# fonte.net
KiCad netlist of a schematic drawn in EAGLE
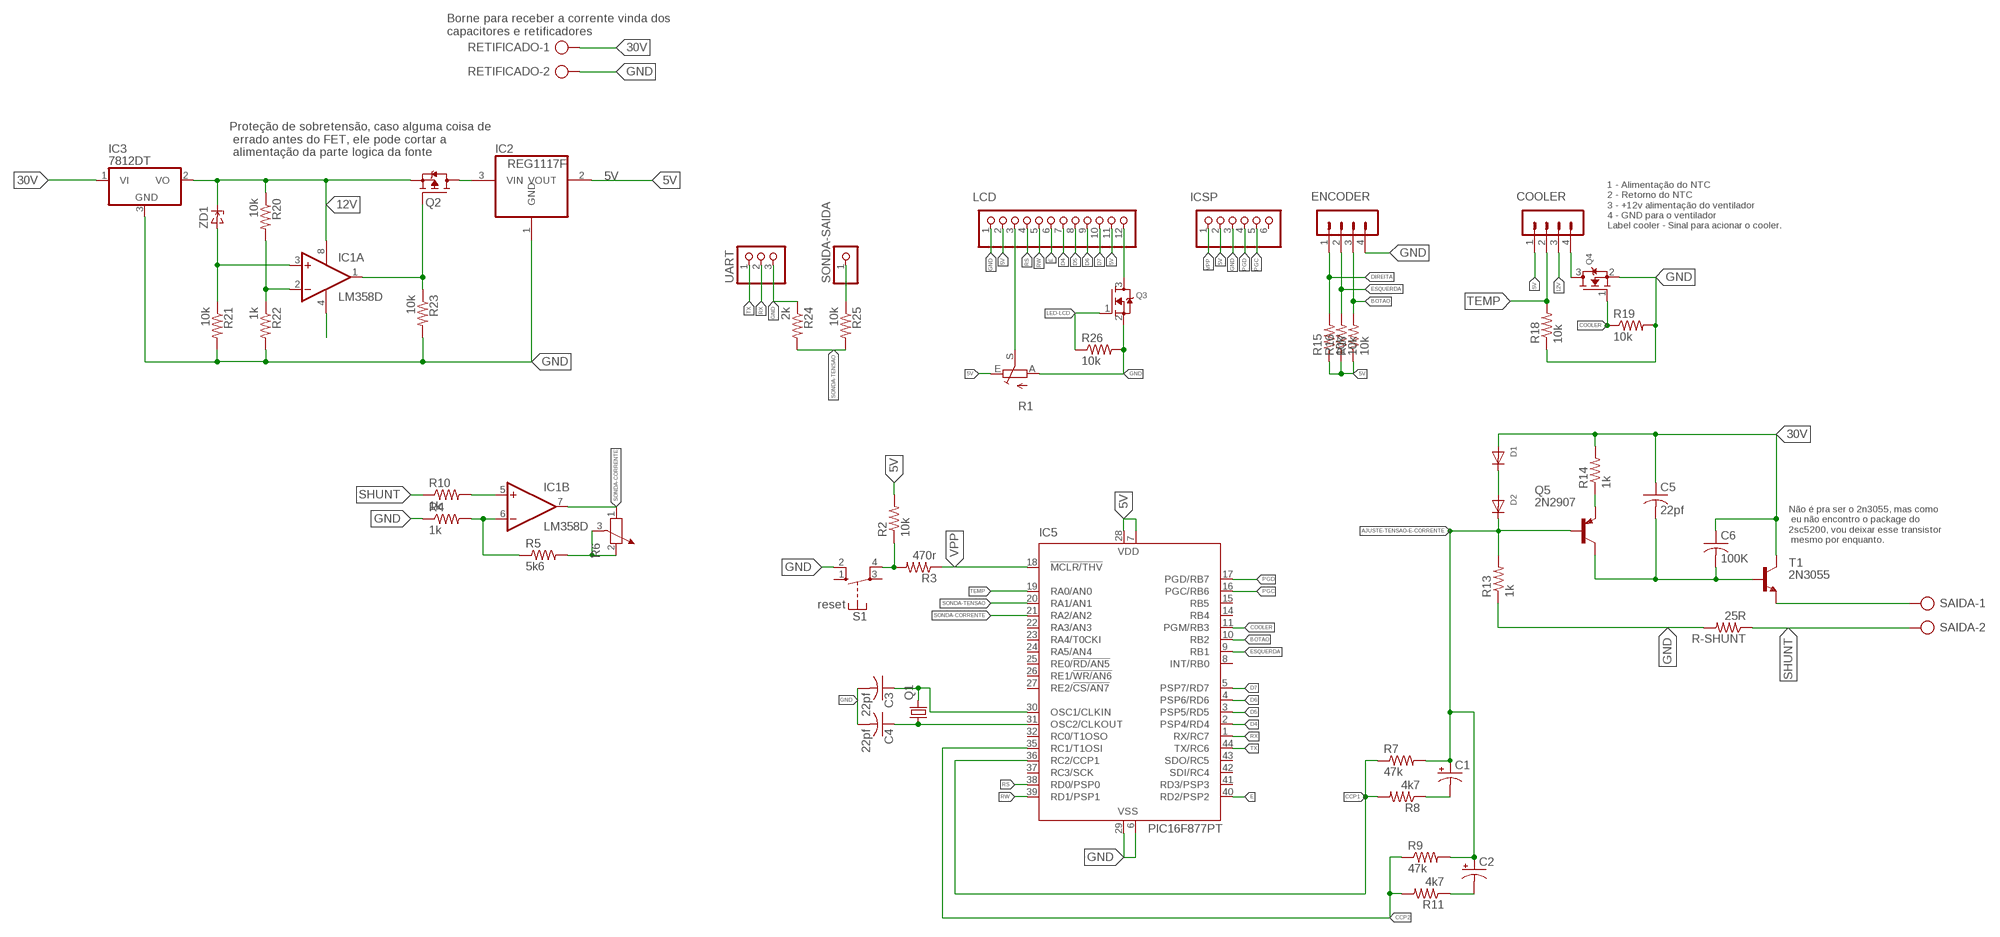
[diagram p0: schematic, sheet 1]

(export (version "E")
  (design (tool "Eeschema 10.0.6"))
  (components
    (comp (ref "C1")
      (value "CPOL-US140CLH-1010")
      (footprint "eagle-import:140CLH-1010")
      (libsource (lib "eagle-import") (part "CPOL-US140CLH-1010"))
    )
    (comp (ref "C2")
      (value "CPOL-US140CLH-1010")
      (footprint "eagle-import:140CLH-1010")
      (libsource (lib "eagle-import") (part "CPOL-US140CLH-1010"))
    )
    (comp (ref "C3")
      (value "22pf")
      (footprint "eagle-import:C1812")
      (libsource (lib "eagle-import") (part "C-USC1812"))
    )
    (comp (ref "C4")
      (value "22pf")
      (footprint "eagle-import:C1812")
      (libsource (lib "eagle-import") (part "C-USC1812"))
    )
    (comp (ref "C5")
      (value "22pf")
      (footprint "eagle-import:C1812")
      (libsource (lib "eagle-import") (part "C-USC1812"))
    )
    (comp (ref "C6")
      (value "100K")
      (footprint "eagle-import:C1812")
      (libsource (lib "eagle-import") (part "C-USC1812"))
    )
    (comp (ref "COOLER")
      (value "MA04-1")
      (footprint "eagle-import:MA04-1")
      (libsource (lib "eagle-import") (part "MA04-1"))
    )
    (comp (ref "D1")
      (value "DIODESOD-123")
      (footprint "eagle-import:SOD-123")
      (libsource (lib "eagle-import") (part "DIODESOD-123"))
    )
    (comp (ref "D2")
      (value "DIODESOD-123")
      (footprint "eagle-import:SOD-123")
      (libsource (lib "eagle-import") (part "DIODESOD-123"))
    )
    (comp (ref "ENCODER")
      (value "MA04-1")
      (footprint "eagle-import:MA04-1")
      (libsource (lib "eagle-import") (part "MA04-1"))
    )
    (comp (ref "IC1")
      (value "LM358D")
      (footprint "eagle-import:SO08")
      (libsource (lib "eagle-import") (part "LM358D"))
    )
    (comp (ref "IC2")
      (value "REG1117F")
      (footprint "eagle-import:DD-3")
      (fields (field (name "MF") "TEXAS INSTRUMENTS") (field (name "MPN") "REG1117FAKTTT"))
      (libsource (lib "eagle-import") (part "REG1117F"))
    )
    (comp (ref "IC3")
      (value "7812DT")
      (footprint "eagle-import:TO252")
      (libsource (lib "eagle-import") (part "78DT12"))
    )
    (comp (ref "IC5")
      (value "PIC16F877PT")
      (footprint "eagle-import:TQFP44")
      (fields (field (name "MF") "MICROCHIP") (field (name "MPN") "PIC16F877-04/PQ"))
      (libsource (lib "eagle-import") (part "PIC16F87PT7"))
    )
    (comp (ref "ICSP")
      (value "PINHD-1X6B")
      (footprint "eagle-import:1X06-BIG")
      (libsource (lib "eagle-import") (part "PINHD-1X6B"))
    )
    (comp (ref "LCD")
      (value "PINHD-1X12-CB")
      (footprint "eagle-import:1X12-CB")
      (libsource (lib "eagle-import") (part "PINHD-1X12-CB"))
    )
    (comp (ref "Q1")
      (value "CRYSTALHC49UP")
      (footprint "eagle-import:HC49UP")
      (libsource (lib "eagle-import") (part "CRYSTALHC49UP"))
    )
    (comp (ref "Q2")
      (value "BSA223SP")
      (footprint "eagle-import:SC75_INFINEON")
      (libsource (lib "eagle-import") (part "BSA223SP"))
    )
    (comp (ref "Q3")
      (value "MOSFET-NREFLOW")
      (footprint "eagle-import:SOT23")
      (libsource (lib "eagle-import") (part "MOSFET-NREFLOW"))
    )
    (comp (ref "Q4")
      (value "MOSFET-NREFLOW")
      (footprint "eagle-import:SOT23")
      (libsource (lib "eagle-import") (part "MOSFET-NREFLOW"))
    )
    (comp (ref "Q5")
      (value "2N2907")
      (footprint "eagle-import:TO92-EBC-OVAL")
      (libsource (lib "eagle-import") (part "2N2907"))
    )
    (comp (ref "R-SHUNT")
      (value "25R")
      (footprint "eagle-import:R0603")
      (libsource (lib "eagle-import") (part "R-US_R0603"))
    )
    (comp (ref "R1")
      (value "TRIM_EU-LI15")
      (footprint "eagle-import:LI15")
      (libsource (lib "eagle-import") (part "TRIM_EU-LI15"))
    )
    (comp (ref "R2")
      (value "10k")
      (footprint "eagle-import:R0603")
      (libsource (lib "eagle-import") (part "R-US_R0603"))
    )
    (comp (ref "R3")
      (value "470r")
      (footprint "eagle-import:R0603")
      (libsource (lib "eagle-import") (part "R-US_R0603"))
    )
    (comp (ref "R4")
      (value "1k")
      (footprint "eagle-import:R0603")
      (libsource (lib "eagle-import") (part "R-US_R0603"))
    )
    (comp (ref "R5")
      (value "5k6")
      (footprint "eagle-import:R0603")
      (libsource (lib "eagle-import") (part "R-US_R0603"))
    )
    (comp (ref "R6")
      (value "POTENTIOMETER_PT-10")
      (footprint "eagle-import:PT-10")
      (libsource (lib "eagle-import") (part "POTENTIOMETER_PT-10"))
    )
    (comp (ref "R7")
      (value "47k")
      (footprint "eagle-import:R0603")
      (libsource (lib "eagle-import") (part "R-US_R0603"))
    )
    (comp (ref "R8")
      (value "4k7")
      (footprint "eagle-import:R0603")
      (libsource (lib "eagle-import") (part "R-US_R0603"))
    )
    (comp (ref "R9")
      (value "47k")
      (footprint "eagle-import:R0603")
      (libsource (lib "eagle-import") (part "R-US_R0603"))
    )
    (comp (ref "R10")
      (value "1k")
      (footprint "eagle-import:R0603")
      (libsource (lib "eagle-import") (part "R-US_R0603"))
    )
    (comp (ref "R11")
      (value "4k7")
      (footprint "eagle-import:R0603")
      (libsource (lib "eagle-import") (part "R-US_R0603"))
    )
    (comp (ref "R13")
      (value "1k")
      (footprint "eagle-import:R0603")
      (libsource (lib "eagle-import") (part "R-US_R0603"))
    )
    (comp (ref "R14")
      (value "1k")
      (footprint "eagle-import:R0603")
      (libsource (lib "eagle-import") (part "R-US_R0603"))
    )
    (comp (ref "R15")
      (value "10k")
      (footprint "eagle-import:R0603")
      (libsource (lib "eagle-import") (part "R-US_R0603"))
    )
    (comp (ref "R16")
      (value "10k")
      (footprint "eagle-import:R0603")
      (libsource (lib "eagle-import") (part "R-US_R0603"))
    )
    (comp (ref "R17")
      (value "10k")
      (footprint "eagle-import:R0603")
      (libsource (lib "eagle-import") (part "R-US_R0603"))
    )
    (comp (ref "R18")
      (value "10k")
      (footprint "eagle-import:R0603")
      (libsource (lib "eagle-import") (part "R-US_R0603"))
    )
    (comp (ref "R19")
      (value "10k")
      (footprint "eagle-import:R0603")
      (libsource (lib "eagle-import") (part "R-US_R0603"))
    )
    (comp (ref "R20")
      (value "10k")
      (footprint "eagle-import:R0603")
      (libsource (lib "eagle-import") (part "R-US_R0603"))
    )
    (comp (ref "R21")
      (value "10k")
      (footprint "eagle-import:R0603")
      (libsource (lib "eagle-import") (part "R-US_R0603"))
    )
    (comp (ref "R22")
      (value "1k")
      (footprint "eagle-import:R0603")
      (libsource (lib "eagle-import") (part "R-US_R0603"))
    )
    (comp (ref "R23")
      (value "10k")
      (footprint "eagle-import:R0603")
      (libsource (lib "eagle-import") (part "R-US_R0603"))
    )
    (comp (ref "R24")
      (value "2k")
      (footprint "eagle-import:R0603")
      (libsource (lib "eagle-import") (part "R-US_R0603"))
    )
    (comp (ref "R25")
      (value "10k")
      (footprint "eagle-import:R0603")
      (libsource (lib "eagle-import") (part "R-US_R0603"))
    )
    (comp (ref "R26")
      (value "10k")
      (footprint "eagle-import:R0603")
      (libsource (lib "eagle-import") (part "R-US_R0603"))
    )
    (comp (ref "RETIFICADO")
      (value "AK300/2")
      (footprint "eagle-import:AK300_2")
      (libsource (lib "eagle-import") (part "AK300/2"))
    )
    (comp (ref "S1")
      (value "reset")
      (footprint "eagle-import:RACON12")
      (libsource (lib "eagle-import") (part "RACON12"))
    )
    (comp (ref "SAIDA")
      (value "AK300/2")
      (footprint "eagle-import:AK300_2")
      (libsource (lib "eagle-import") (part "AK300/2"))
    )
    (comp (ref "SONDA-SAIDA")
      (value "PINHD-1X1")
      (footprint "eagle-import:1X01")
      (libsource (lib "eagle-import") (part "PINHD-1X1"))
    )
    (comp (ref "T1")
      (value "2N3055")
      (footprint "eagle-import:TO3")
      (libsource (lib "eagle-import") (part "2N3055"))
    )
    (comp (ref "UART")
      (value "PINHD-1X3CB")
      (footprint "eagle-import:1X03-CLEANBIG")
      (libsource (lib "eagle-import") (part "PINHD-1X3CB"))
    )
    (comp (ref "ZD1")
      (value "ZENERSOD-123")
      (footprint "eagle-import:SOD-123")
      (libsource (lib "eagle-import") (part "ZENERSOD-123"))
    )
  )
  (nets
    (net (code "1") (name "5V") (class "Default")
      (node (ref "COOLER") (pin "1") (pinfunction "1_1") (pintype "passive"))
      (node (ref "IC2") (pin "2") (pinfunction "VOUT_2") (pintype "output"))
      (node (ref "IC5") (pin "28") (pinfunction "VDD_28") (pintype "power_in"))
      (node (ref "IC5") (pin "7") (pinfunction "VDD_7") (pintype "power_in"))
      (node (ref "ICSP") (pin "2") (pinfunction "2_2") (pintype "passive"))
      (node (ref "LCD") (pin "11") (pinfunction "11_11") (pintype "passive"))
      (node (ref "LCD") (pin "2") (pinfunction "2_2") (pintype "passive"))
      (node (ref "R1") (pin "E") (pinfunction "E_E") (pintype "passive"))
      (node (ref "R15") (pin "1") (pinfunction "1_1") (pintype "passive"))
      (node (ref "R16") (pin "1") (pinfunction "1_1") (pintype "passive"))
      (node (ref "R17") (pin "1") (pinfunction "1_1") (pintype "passive"))
      (node (ref "R2") (pin "2") (pinfunction "2_2") (pintype "passive"))
    )
    (net (code "2") (name "12V") (class "Default")
      (node (ref "COOLER") (pin "3") (pinfunction "3_3") (pintype "passive"))
      (node (ref "IC1") (pin "8") (pinfunction "V+_8") (pintype "power_in"))
      (node (ref "IC3") (pin "2") (pinfunction "VO_2") (pintype "passive"))
      (node (ref "Q2") (pin "3") (pinfunction "S_3") (pintype "passive"))
      (node (ref "R20") (pin "1") (pinfunction "1_1") (pintype "passive"))
      (node (ref "ZD1") (pin "C") (pinfunction "C_C") (pintype "passive"))
    )
    (net (code "3") (name "30V") (class "Default")
      (node (ref "C5") (pin "1") (pinfunction "1_1") (pintype "passive"))
      (node (ref "C6") (pin "1") (pinfunction "1_1") (pintype "passive"))
      (node (ref "D1") (pin "A") (pinfunction "A_A") (pintype "passive"))
      (node (ref "IC3") (pin "1") (pinfunction "VI_1") (pintype "input"))
      (node (ref "R14") (pin "2") (pinfunction "2_2") (pintype "passive"))
      (node (ref "RETIFICADO") (pin "1") (pinfunction "KL_1") (pintype "passive"))
      (node (ref "T1") (pin "C") (pinfunction "C_C") (pintype "passive"))
      (node (ref "T1") (pin "C/") (pinfunction "C_C/") (pintype "passive"))
    )
    (net (code "4") (name "AJUSTE-TENSAO-E-CORRENTE") (class "Default")
      (node (ref "C1") (pin "+") (pinfunction "+_+") (pintype "passive"))
      (node (ref "C2") (pin "+") (pinfunction "+_+") (pintype "passive"))
      (node (ref "D2") (pin "C") (pinfunction "C_C") (pintype "passive"))
      (node (ref "Q5") (pin "B") (pinfunction "B_B") (pintype "passive"))
      (node (ref "R13") (pin "2") (pinfunction "2_2") (pintype "passive"))
      (node (ref "R7") (pin "2") (pinfunction "2_2") (pintype "passive"))
      (node (ref "R9") (pin "2") (pinfunction "2_2") (pintype "passive"))
    )
    (net (code "5") (name "BOTAO") (class "Default")
      (node (ref "ENCODER") (pin "3") (pinfunction "3_3") (pintype "passive"))
      (node (ref "IC5") (pin "10") (pinfunction "RB2_10") (pintype "bidirectional"))
      (node (ref "R17") (pin "2") (pinfunction "2_2") (pintype "passive"))
    )
    (net (code "6") (name "CCP1") (class "Default")
      (node (ref "IC5") (pin "36") (pinfunction "RC2/CCP1_36") (pintype "bidirectional"))
      (node (ref "R7") (pin "1") (pinfunction "1_1") (pintype "passive"))
      (node (ref "R8") (pin "2") (pinfunction "2_2") (pintype "passive"))
    )
    (net (code "7") (name "CCP2") (class "Default")
      (node (ref "IC5") (pin "35") (pinfunction "RC1/T1OSI_35") (pintype "bidirectional"))
      (node (ref "R11") (pin "2") (pinfunction "2_2") (pintype "passive"))
      (node (ref "R9") (pin "1") (pinfunction "1_1") (pintype "passive"))
    )
    (net (code "8") (name "COOLER") (class "Default")
      (node (ref "IC5") (pin "11") (pinfunction "PGM/RB3_11") (pintype "bidirectional"))
      (node (ref "Q4") (pin "1") (pinfunction "G_1") (pintype "bidirectional"))
      (node (ref "R19") (pin "1") (pinfunction "1_1") (pintype "passive"))
    )
    (net (code "9") (name "D4") (class "Default")
      (node (ref "IC5") (pin "2") (pinfunction "PSP4/RD4_2") (pintype "bidirectional"))
      (node (ref "LCD") (pin "7") (pinfunction "7_7") (pintype "passive"))
    )
    (net (code "10") (name "D5") (class "Default")
      (node (ref "IC5") (pin "3") (pinfunction "PSP5/RD5_3") (pintype "bidirectional"))
      (node (ref "LCD") (pin "8") (pinfunction "8_8") (pintype "passive"))
    )
    (net (code "11") (name "D6") (class "Default")
      (node (ref "IC5") (pin "4") (pinfunction "PSP6/RD6_4") (pintype "bidirectional"))
      (node (ref "LCD") (pin "9") (pinfunction "9_9") (pintype "passive"))
    )
    (net (code "12") (name "D7") (class "Default")
      (node (ref "IC5") (pin "5") (pinfunction "PSP7/RD7_5") (pintype "bidirectional"))
      (node (ref "LCD") (pin "10") (pinfunction "10_10") (pintype "passive"))
    )
    (net (code "13") (name "DIREITA") (class "Default")
      (node (ref "ENCODER") (pin "1") (pinfunction "1_1") (pintype "passive"))
      (node (ref "R15") (pin "2") (pinfunction "2_2") (pintype "passive"))
    )
    (net (code "14") (name "E") (class "Default")
      (node (ref "IC5") (pin "40") (pinfunction "RD2/PSP2_40") (pintype "bidirectional"))
      (node (ref "LCD") (pin "6") (pinfunction "6_6") (pintype "passive"))
    )
    (net (code "15") (name "ESQUERDA") (class "Default")
      (node (ref "ENCODER") (pin "2") (pinfunction "2_2") (pintype "passive"))
      (node (ref "IC5") (pin "9") (pinfunction "RB1_9") (pintype "bidirectional"))
      (node (ref "R16") (pin "2") (pinfunction "2_2") (pintype "passive"))
    )
    (net (code "16") (name "GND") (class "Default")
      (node (ref "C1") (pin "-") (pinfunction "-_-") (pintype "passive"))
      (node (ref "C2") (pin "-") (pinfunction "-_-") (pintype "passive"))
      (node (ref "C3") (pin "2") (pinfunction "2_2") (pintype "passive"))
      (node (ref "C4") (pin "2") (pinfunction "2_2") (pintype "passive"))
      (node (ref "ENCODER") (pin "4") (pinfunction "4_4") (pintype "passive"))
      (node (ref "IC2") (pin "1") (pinfunction "GND_1") (pintype "power_in"))
      (node (ref "IC3") (pin "3") (pinfunction "GND_3") (pintype "passive"))
      (node (ref "IC5") (pin "29") (pinfunction "VSS_29") (pintype "power_in"))
      (node (ref "IC5") (pin "6") (pinfunction "VSS_6") (pintype "power_in"))
      (node (ref "ICSP") (pin "3") (pinfunction "3_3") (pintype "passive"))
      (node (ref "LCD") (pin "1") (pinfunction "1_1") (pintype "passive"))
      (node (ref "Q3") (pin "2") (pinfunction "S_2") (pintype "bidirectional"))
      (node (ref "Q4") (pin "2") (pinfunction "S_2") (pintype "bidirectional"))
      (node (ref "R-SHUNT") (pin "2") (pinfunction "2_2") (pintype "passive"))
      (node (ref "R1") (pin "A") (pinfunction "A_A") (pintype "passive"))
      (node (ref "R11") (pin "1") (pinfunction "1_1") (pintype "passive"))
      (node (ref "R13") (pin "1") (pinfunction "1_1") (pintype "passive"))
      (node (ref "R18") (pin "1") (pinfunction "1_1") (pintype "passive"))
      (node (ref "R19") (pin "2") (pinfunction "2_2") (pintype "passive"))
      (node (ref "R21") (pin "2") (pinfunction "2_2") (pintype "passive"))
      (node (ref "R22") (pin "2") (pinfunction "2_2") (pintype "passive"))
      (node (ref "R23") (pin "2") (pinfunction "2_2") (pintype "passive"))
      (node (ref "R24") (pin "1") (pinfunction "1_1") (pintype "passive"))
      (node (ref "R26") (pin "2") (pinfunction "2_2") (pintype "passive"))
      (node (ref "R4") (pin "1") (pinfunction "1_1") (pintype "passive"))
      (node (ref "R8") (pin "1") (pinfunction "1_1") (pintype "passive"))
      (node (ref "RETIFICADO") (pin "2") (pinfunction "KL_2") (pintype "passive"))
      (node (ref "S1") (pin "2") (pinfunction "S_2") (pintype "passive"))
      (node (ref "UART") (pin "3") (pinfunction "3_3") (pintype "passive"))
    )
    (net (code "17") (name "LED-LCD") (class "Default")
      (node (ref "Q3") (pin "1") (pinfunction "G_1") (pintype "bidirectional"))
      (node (ref "R26") (pin "1") (pinfunction "1_1") (pintype "passive"))
    )
    (net (code "18") (name "Net-(C5-Pad2)") (class "Default")
      (node (ref "C5") (pin "2") (pinfunction "2_2") (pintype "passive"))
      (node (ref "C6") (pin "2") (pinfunction "2_2") (pintype "passive"))
      (node (ref "Q5") (pin "C") (pinfunction "C_C") (pintype "passive"))
      (node (ref "T1") (pin "B") (pinfunction "B_B") (pintype "passive"))
    )
    (net (code "19") (name "Net-(D1-PadC)") (class "Default")
      (node (ref "D1") (pin "C") (pinfunction "C_C") (pintype "passive"))
      (node (ref "D2") (pin "A") (pinfunction "A_A") (pintype "passive"))
    )
    (net (code "20") (name "Net-(IC1A-+IN)") (class "Default")
      (node (ref "IC1") (pin "3") (pinfunction "+IN_3") (pintype "input"))
      (node (ref "R21") (pin "1") (pinfunction "1_1") (pintype "passive"))
      (node (ref "ZD1") (pin "A") (pinfunction "A_A") (pintype "passive"))
    )
    (net (code "21") (name "Net-(IC1A--IN)") (class "Default")
      (node (ref "IC1") (pin "2") (pinfunction "-IN_2") (pintype "input"))
      (node (ref "R20") (pin "2") (pinfunction "2_2") (pintype "passive"))
      (node (ref "R22") (pin "1") (pinfunction "1_1") (pintype "passive"))
    )
    (net (code "22") (name "Net-(IC1A-OUT)") (class "Default")
      (node (ref "IC1") (pin "1") (pinfunction "OUT_1") (pintype "output"))
      (node (ref "Q2") (pin "1") (pinfunction "G_1") (pintype "passive"))
      (node (ref "R23") (pin "1") (pinfunction "1_1") (pintype "passive"))
    )
    (net (code "23") (name "Net-(IC1B-+IN)") (class "Default")
      (node (ref "IC1") (pin "5") (pinfunction "+IN_5") (pintype "input"))
      (node (ref "R10") (pin "2") (pinfunction "2_2") (pintype "passive"))
    )
    (net (code "24") (name "Net-(IC1B--IN)") (class "Default")
      (node (ref "IC1") (pin "6") (pinfunction "-IN_6") (pintype "input"))
      (node (ref "R4") (pin "2") (pinfunction "2_2") (pintype "passive"))
      (node (ref "R5") (pin "1") (pinfunction "1_1") (pintype "passive"))
    )
    (net (code "25") (name "Net-(IC2-VIN)") (class "Default")
      (node (ref "IC2") (pin "3") (pinfunction "VIN_3") (pintype "input"))
      (node (ref "Q2") (pin "2") (pinfunction "D_2") (pintype "passive"))
    )
    (net (code "26") (name "Net-(IC5-OSC1{slash}CLKIN)") (class "Default")
      (node (ref "C3") (pin "1") (pinfunction "1_1") (pintype "passive"))
      (node (ref "IC5") (pin "30") (pinfunction "OSC1/CLKIN_30") (pintype "input"))
      (node (ref "Q1") (pin "2") (pinfunction "2_2") (pintype "passive"))
    )
    (net (code "27") (name "Net-(IC5-OSC2{slash}CLKOUT)") (class "Default")
      (node (ref "C4") (pin "1") (pinfunction "1_1") (pintype "passive"))
      (node (ref "IC5") (pin "31") (pinfunction "OSC2/CLKOUT_31") (pintype "output"))
      (node (ref "Q1") (pin "1") (pinfunction "1_1") (pintype "passive"))
    )
    (net (code "28") (name "Net-(LCD-Pad3)") (class "Default")
      (node (ref "LCD") (pin "3") (pinfunction "3_3") (pintype "passive"))
      (node (ref "R1") (pin "S") (pinfunction "S_S") (pintype "passive"))
    )
    (net (code "29") (name "Net-(Q3-D)") (class "Default")
      (node (ref "LCD") (pin "12") (pinfunction "12_12") (pintype "passive"))
      (node (ref "Q3") (pin "3") (pinfunction "D_3") (pintype "bidirectional"))
    )
    (net (code "30") (name "Net-(Q4-D)") (class "Default")
      (node (ref "COOLER") (pin "4") (pinfunction "4_4") (pintype "passive"))
      (node (ref "Q4") (pin "3") (pinfunction "D_3") (pintype "bidirectional"))
    )
    (net (code "31") (name "Net-(Q5-PadE)") (class "Default")
      (node (ref "Q5") (pin "E") (pinfunction "E_E") (pintype "passive"))
      (node (ref "R14") (pin "1") (pinfunction "1_1") (pintype "passive"))
    )
    (net (code "32") (name "Net-(R2-Pad1)") (class "Default")
      (node (ref "R2") (pin "1") (pinfunction "1_1") (pintype "passive"))
      (node (ref "R3") (pin "2") (pinfunction "2_2") (pintype "passive"))
      (node (ref "S1") (pin "4") (pinfunction "P_4") (pintype "passive"))
    )
    (net (code "33") (name "Net-(R5-Pad2)") (class "Default")
      (node (ref "R5") (pin "2") (pinfunction "2_2") (pintype "passive"))
      (node (ref "R6") (pin "2") (pinfunction "2_2") (pintype "passive"))
      (node (ref "R6") (pin "3") (pinfunction "3_3") (pintype "passive"))
    )
    (net (code "34") (name "Net-(R25-Pad1)") (class "Default")
      (node (ref "R25") (pin "1") (pinfunction "1_1") (pintype "passive"))
      (node (ref "SONDA-SAIDA") (pin "1") (pinfunction "1_1") (pintype "passive"))
    )
    (net (code "35") (name "Net-(SAIDAA-KL)") (class "Default")
      (node (ref "SAIDA") (pin "1") (pinfunction "KL_1") (pintype "passive"))
      (node (ref "T1") (pin "E") (pinfunction "E_E") (pintype "passive"))
    )
    (net (code "36") (name "PGC") (class "Default")
      (node (ref "IC5") (pin "16") (pinfunction "PGC/RB6_16") (pintype "bidirectional"))
      (node (ref "ICSP") (pin "5") (pinfunction "5_5") (pintype "passive"))
    )
    (net (code "37") (name "PGD") (class "Default")
      (node (ref "IC5") (pin "17") (pinfunction "PGD/RB7_17") (pintype "bidirectional"))
      (node (ref "ICSP") (pin "4") (pinfunction "4_4") (pintype "passive"))
    )
    (net (code "38") (name "RS") (class "Default")
      (node (ref "IC5") (pin "38") (pinfunction "RD0/PSP0_38") (pintype "bidirectional"))
      (node (ref "LCD") (pin "4") (pinfunction "4_4") (pintype "passive"))
    )
    (net (code "39") (name "RW") (class "Default")
      (node (ref "IC5") (pin "39") (pinfunction "RD1/PSP1_39") (pintype "bidirectional"))
      (node (ref "LCD") (pin "5") (pinfunction "5_5") (pintype "passive"))
    )
    (net (code "40") (name "RX") (class "Default")
      (node (ref "IC5") (pin "1") (pinfunction "RX/RC7_1") (pintype "bidirectional"))
      (node (ref "UART") (pin "2") (pinfunction "2_2") (pintype "passive"))
    )
    (net (code "41") (name "SHUNT") (class "Default")
      (node (ref "R-SHUNT") (pin "1") (pinfunction "1_1") (pintype "passive"))
      (node (ref "R10") (pin "1") (pinfunction "1_1") (pintype "passive"))
      (node (ref "SAIDA") (pin "2") (pinfunction "KL_2") (pintype "passive"))
    )
    (net (code "42") (name "SONDA-CORRENTE") (class "Default")
      (node (ref "IC1") (pin "7") (pinfunction "OUT_7") (pintype "output"))
      (node (ref "IC5") (pin "21") (pinfunction "RA2/AN2_21") (pintype "bidirectional"))
      (node (ref "R6") (pin "1") (pinfunction "1_1") (pintype "passive"))
    )
    (net (code "43") (name "SONDA-TENSAO") (class "Default")
      (node (ref "IC5") (pin "20") (pinfunction "RA1/AN1_20") (pintype "bidirectional"))
      (node (ref "R24") (pin "2") (pinfunction "2_2") (pintype "passive"))
      (node (ref "R25") (pin "2") (pinfunction "2_2") (pintype "passive"))
    )
    (net (code "44") (name "TEMP") (class "Default")
      (node (ref "COOLER") (pin "2") (pinfunction "2_2") (pintype "passive"))
      (node (ref "IC5") (pin "19") (pinfunction "RA0/AN0_19") (pintype "bidirectional"))
      (node (ref "R18") (pin "2") (pinfunction "2_2") (pintype "passive"))
    )
    (net (code "45") (name "TX") (class "Default")
      (node (ref "IC5") (pin "44") (pinfunction "TX/RC6_44") (pintype "bidirectional"))
      (node (ref "UART") (pin "1") (pinfunction "1_1") (pintype "passive"))
    )
    (net (code "46") (name "VPP") (class "Default")
      (node (ref "IC5") (pin "18") (pinfunction "~{MCLR/THV}_18") (pintype "input"))
      (node (ref "ICSP") (pin "1") (pinfunction "1_1") (pintype "passive"))
      (node (ref "R3") (pin "1") (pinfunction "1_1") (pintype "passive"))
    )
    (net (code "47") (name "unconnected-(IC1C-V--Pad4)") (class "Default")
      (node (ref "IC1") (pin "4") (pinfunction "V-_4") (pintype "power_in"))
    )
    (net (code "48") (name "unconnected-(IC5-INT{slash}RB0-Pad8)") (class "Default")
      (node (ref "IC5") (pin "8") (pinfunction "INT/RB0_8") (pintype "bidirectional"))
    )
    (net (code "49") (name "unconnected-(IC5-RA3{slash}AN3-Pad22)") (class "Default")
      (node (ref "IC5") (pin "22") (pinfunction "RA3/AN3_22") (pintype "bidirectional"))
    )
    (net (code "50") (name "unconnected-(IC5-RA4{slash}T0CKI-Pad23)") (class "Default")
      (node (ref "IC5") (pin "23") (pinfunction "RA4/T0CKI_23") (pintype "bidirectional"))
    )
    (net (code "51") (name "unconnected-(IC5-RA5{slash}AN4-Pad24)") (class "Default")
      (node (ref "IC5") (pin "24") (pinfunction "RA5/AN4_24") (pintype "bidirectional"))
    )
    (net (code "52") (name "unconnected-(IC5-RB4-Pad14)") (class "Default")
      (node (ref "IC5") (pin "14") (pinfunction "RB4_14") (pintype "bidirectional"))
    )
    (net (code "53") (name "unconnected-(IC5-RB5-Pad15)") (class "Default")
      (node (ref "IC5") (pin "15") (pinfunction "RB5_15") (pintype "bidirectional"))
    )
    (net (code "54") (name "unconnected-(IC5-RC0{slash}T1OSO-Pad32)") (class "Default")
      (node (ref "IC5") (pin "32") (pinfunction "RC0/T1OSO_32") (pintype "bidirectional"))
    )
    (net (code "55") (name "unconnected-(IC5-RC3{slash}SCK-Pad37)") (class "Default")
      (node (ref "IC5") (pin "37") (pinfunction "RC3/SCK_37") (pintype "bidirectional"))
    )
    (net (code "56") (name "unconnected-(IC5-RD3{slash}PSP3-Pad41)") (class "Default")
      (node (ref "IC5") (pin "41") (pinfunction "RD3/PSP3_41") (pintype "bidirectional"))
    )
    (net (code "57") (name "unconnected-(IC5-RE0{slash}~{RD{slash}AN5}-Pad25)") (class "Default")
      (node (ref "IC5") (pin "25") (pinfunction "RE0/~{RD/AN5}_25") (pintype "bidirectional"))
    )
    (net (code "58") (name "unconnected-(IC5-RE1{slash}~{WR{slash}AN6}-Pad26)") (class "Default")
      (node (ref "IC5") (pin "26") (pinfunction "RE1/~{WR/AN6}_26") (pintype "bidirectional"))
    )
    (net (code "59") (name "unconnected-(IC5-RE2{slash}~{CS{slash}AN7}-Pad27)") (class "Default")
      (node (ref "IC5") (pin "27") (pinfunction "RE2/~{CS/AN7}_27") (pintype "bidirectional"))
    )
    (net (code "60") (name "unconnected-(IC5-SDI{slash}RC4-Pad42)") (class "Default")
      (node (ref "IC5") (pin "42") (pinfunction "SDI/RC4_42") (pintype "bidirectional"))
    )
    (net (code "61") (name "unconnected-(IC5-SDO{slash}RC5-Pad43)") (class "Default")
      (node (ref "IC5") (pin "43") (pinfunction "SDO/RC5_43") (pintype "bidirectional"))
    )
    (net (code "62") (name "unconnected-(ICSP-Pad6)") (class "Default")
      (node (ref "ICSP") (pin "6") (pinfunction "6_6") (pintype "passive"))
    )
    (net (code "63") (name "unconnected-(S1-P-Pad3)") (class "Default")
      (node (ref "S1") (pin "3") (pinfunction "P_3") (pintype "passive"))
    )
    (net (code "64") (name "unconnected-(S1-S-Pad1)") (class "Default")
      (node (ref "S1") (pin "1") (pinfunction "S_1") (pintype "passive"))
    )
  )
)
